# 16ChFNIRS.net
KiCad netlist of a schematic drawn in EAGLE
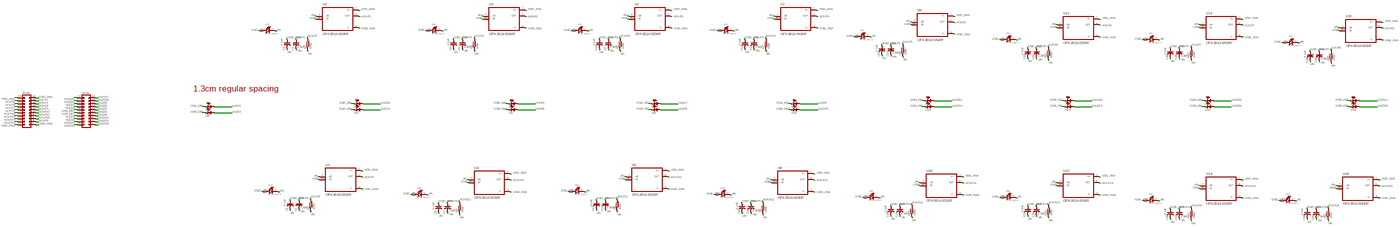
[diagram p0: schematic, sheet 1, overview]
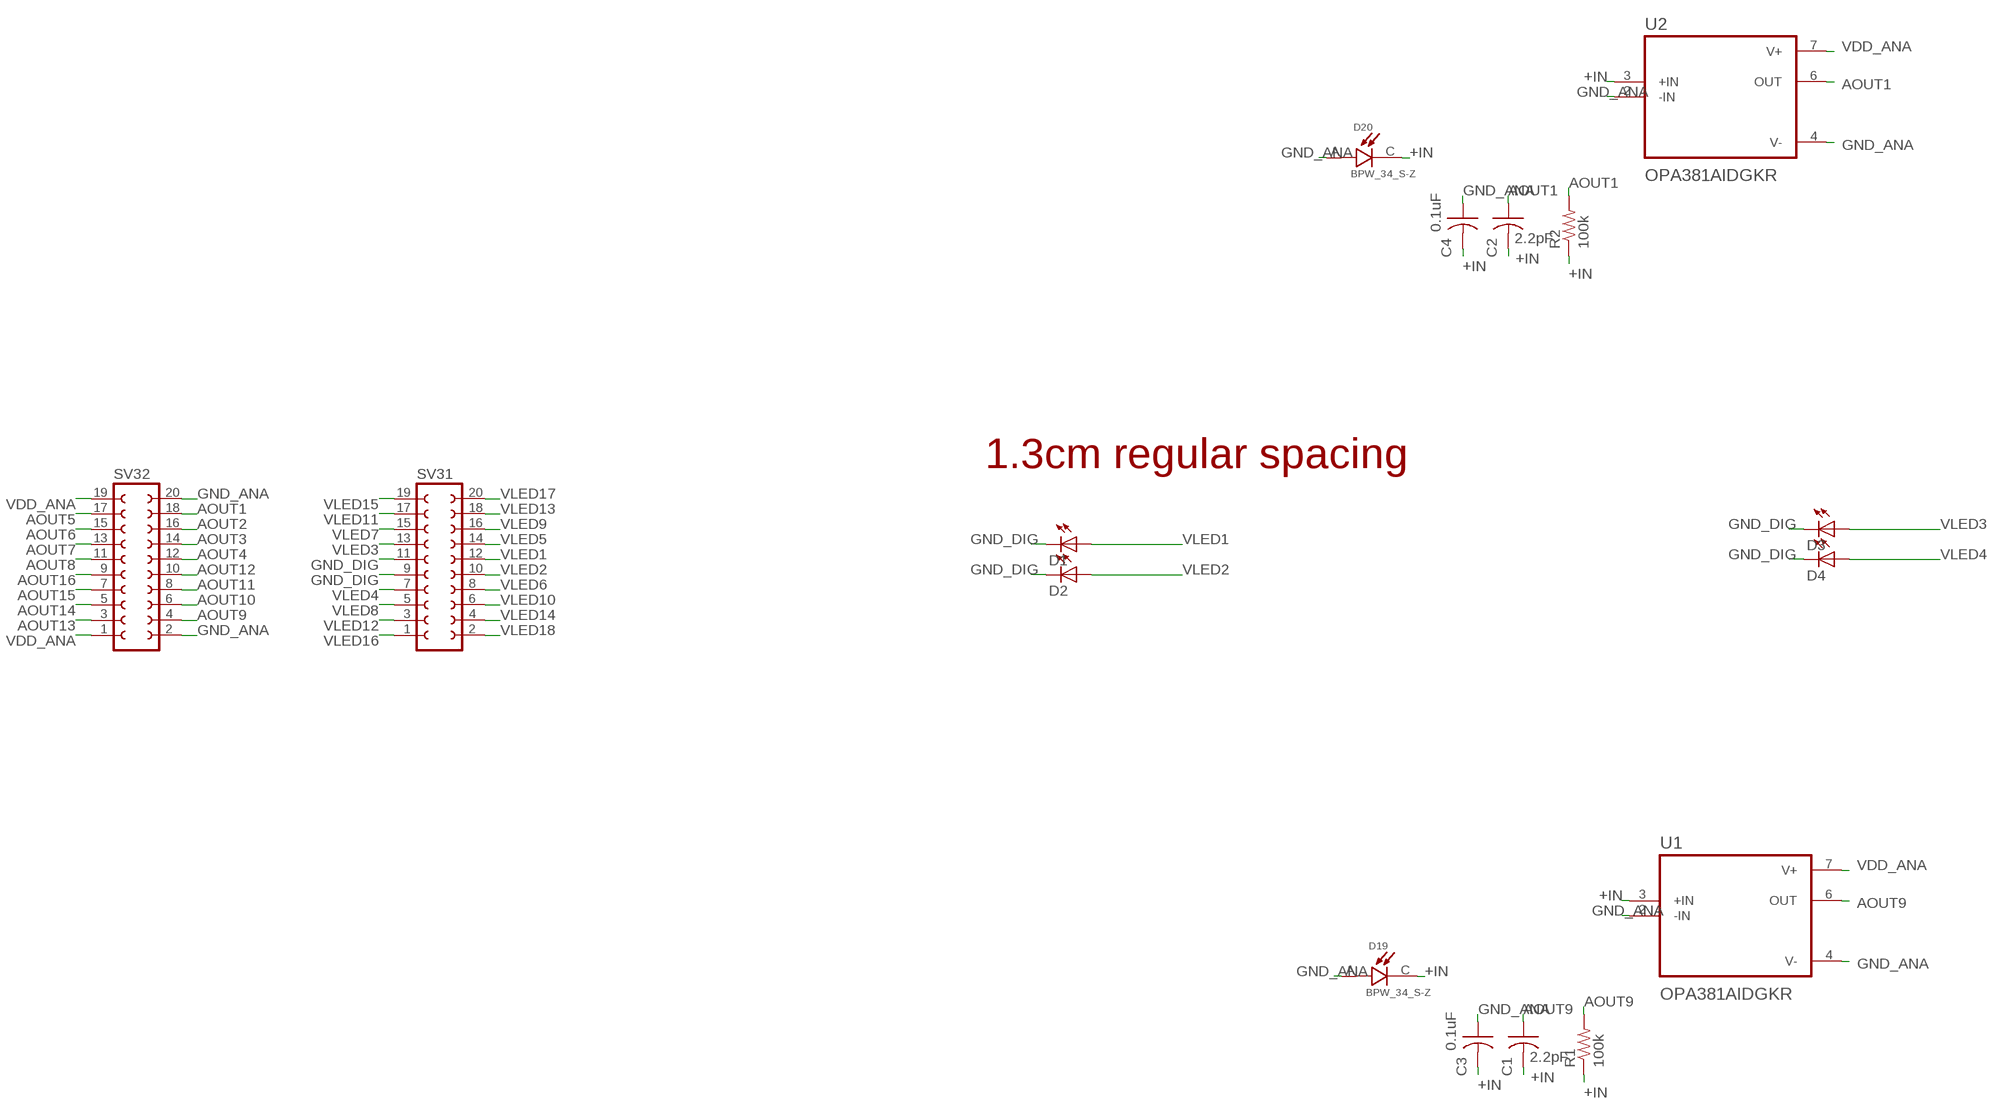
[diagram p1: schematic, sheet 1, part 1 of 4]
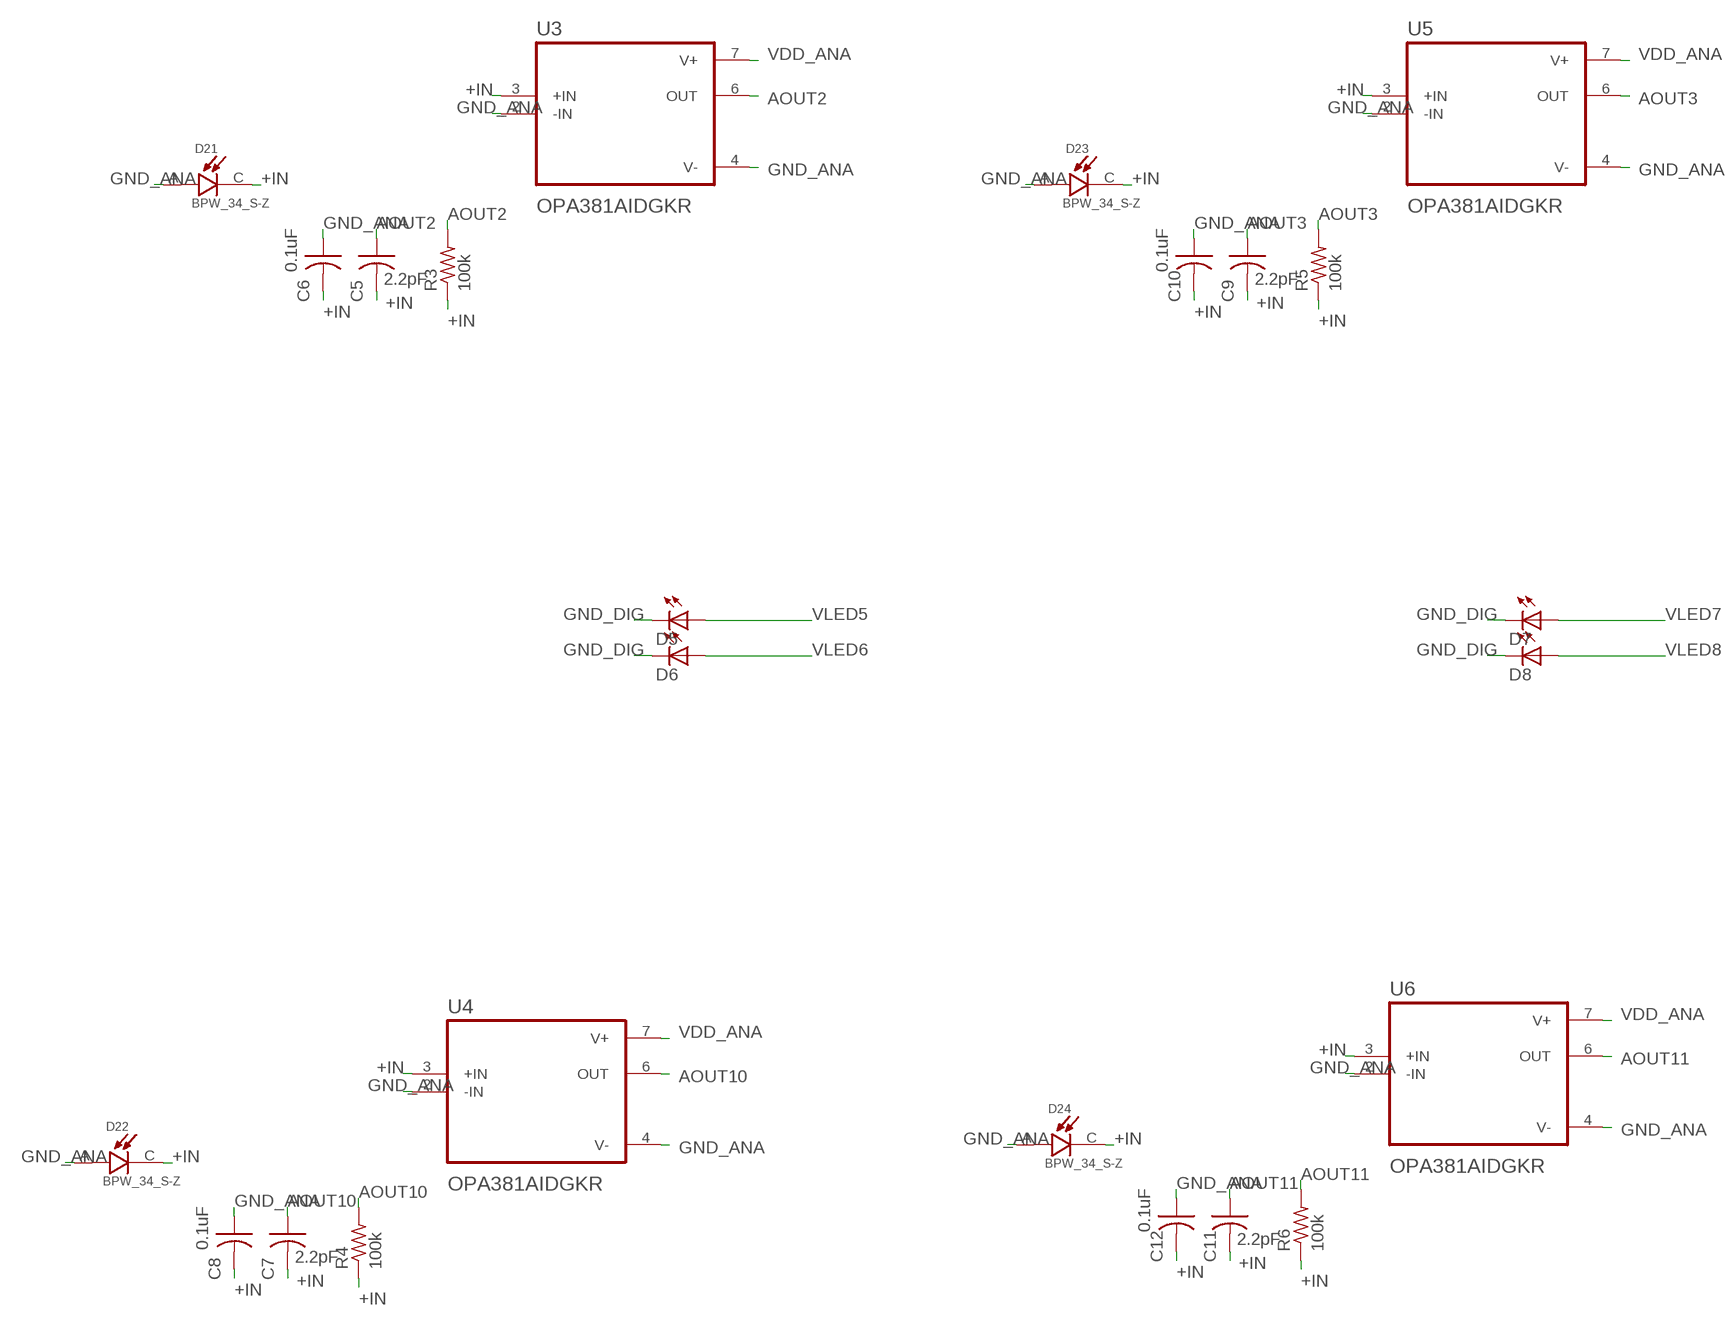
[diagram p2: schematic, sheet 1, part 2 of 4]
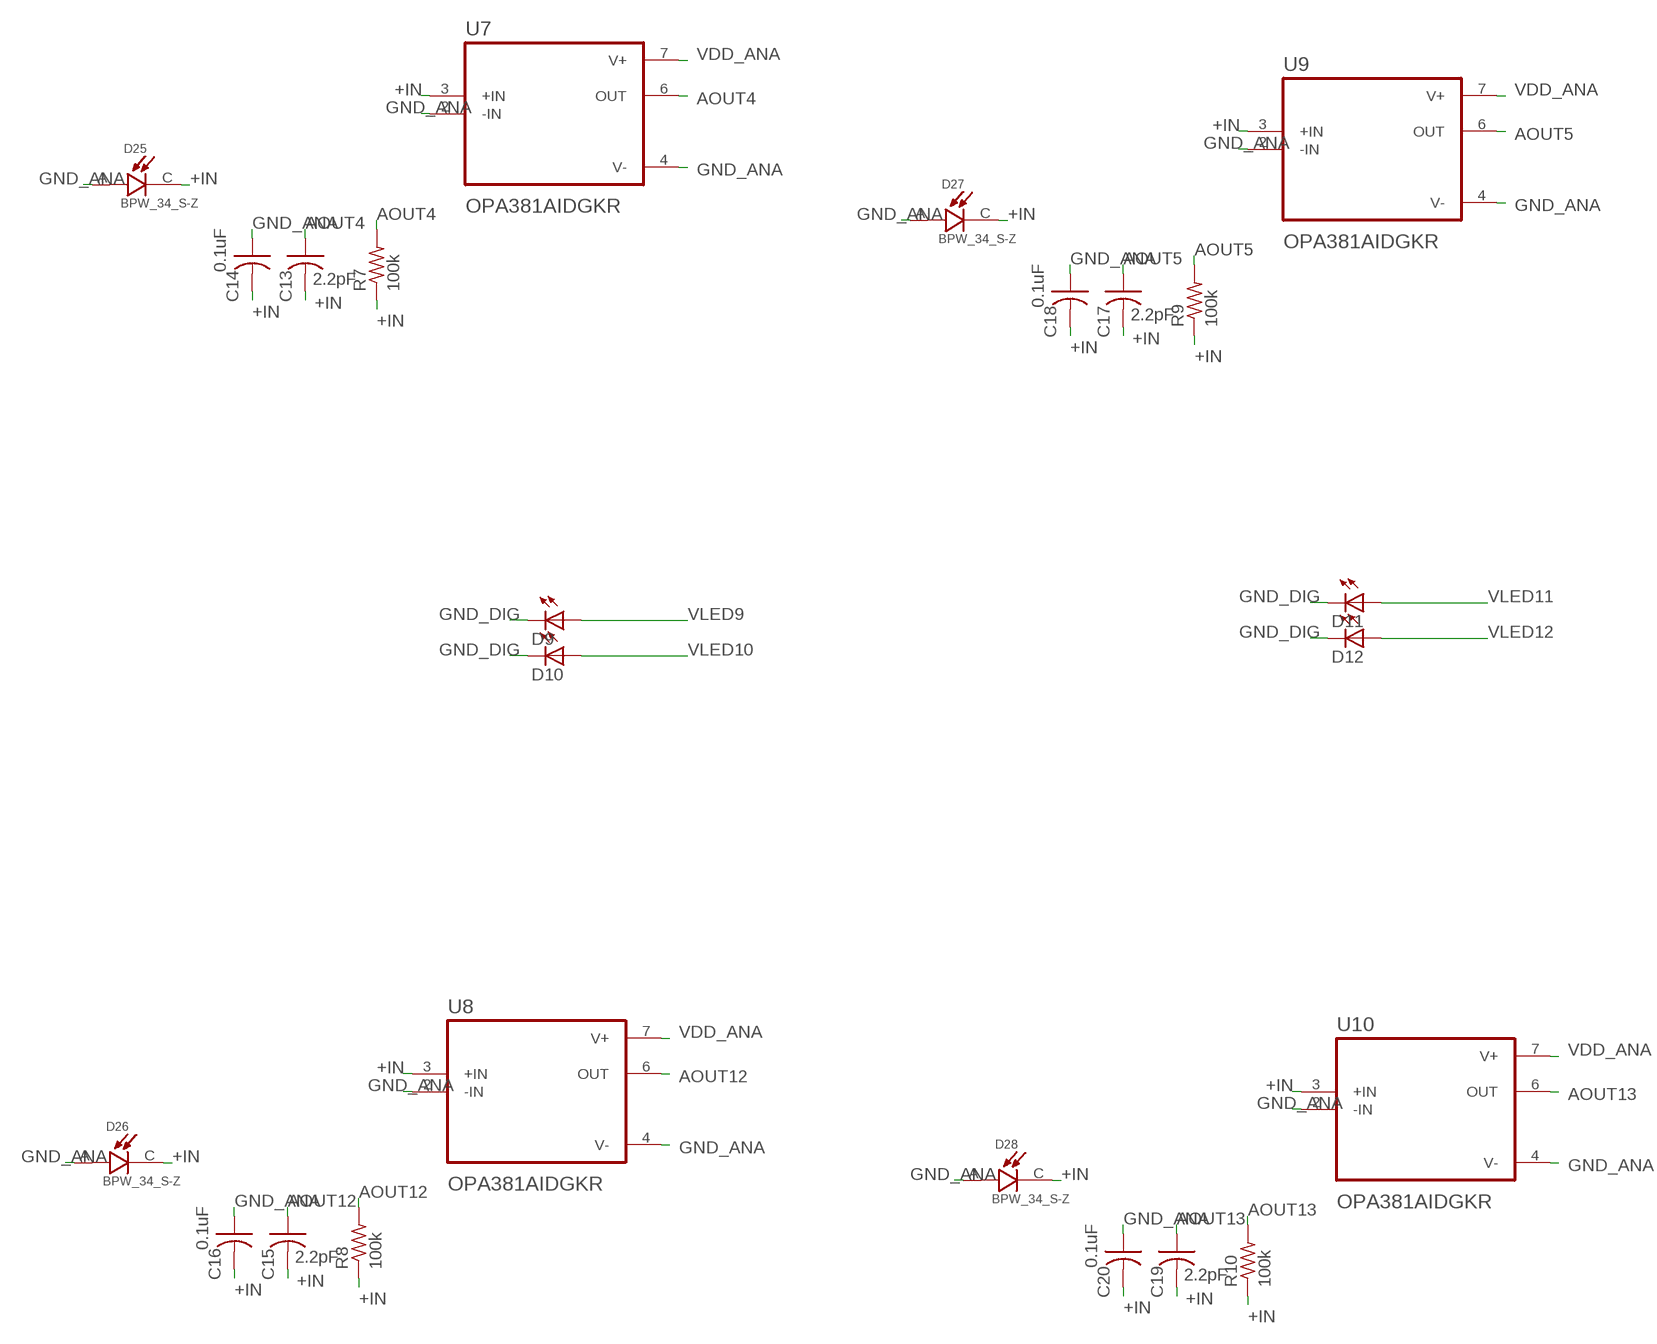
[diagram p3: schematic, sheet 1, part 3 of 4]
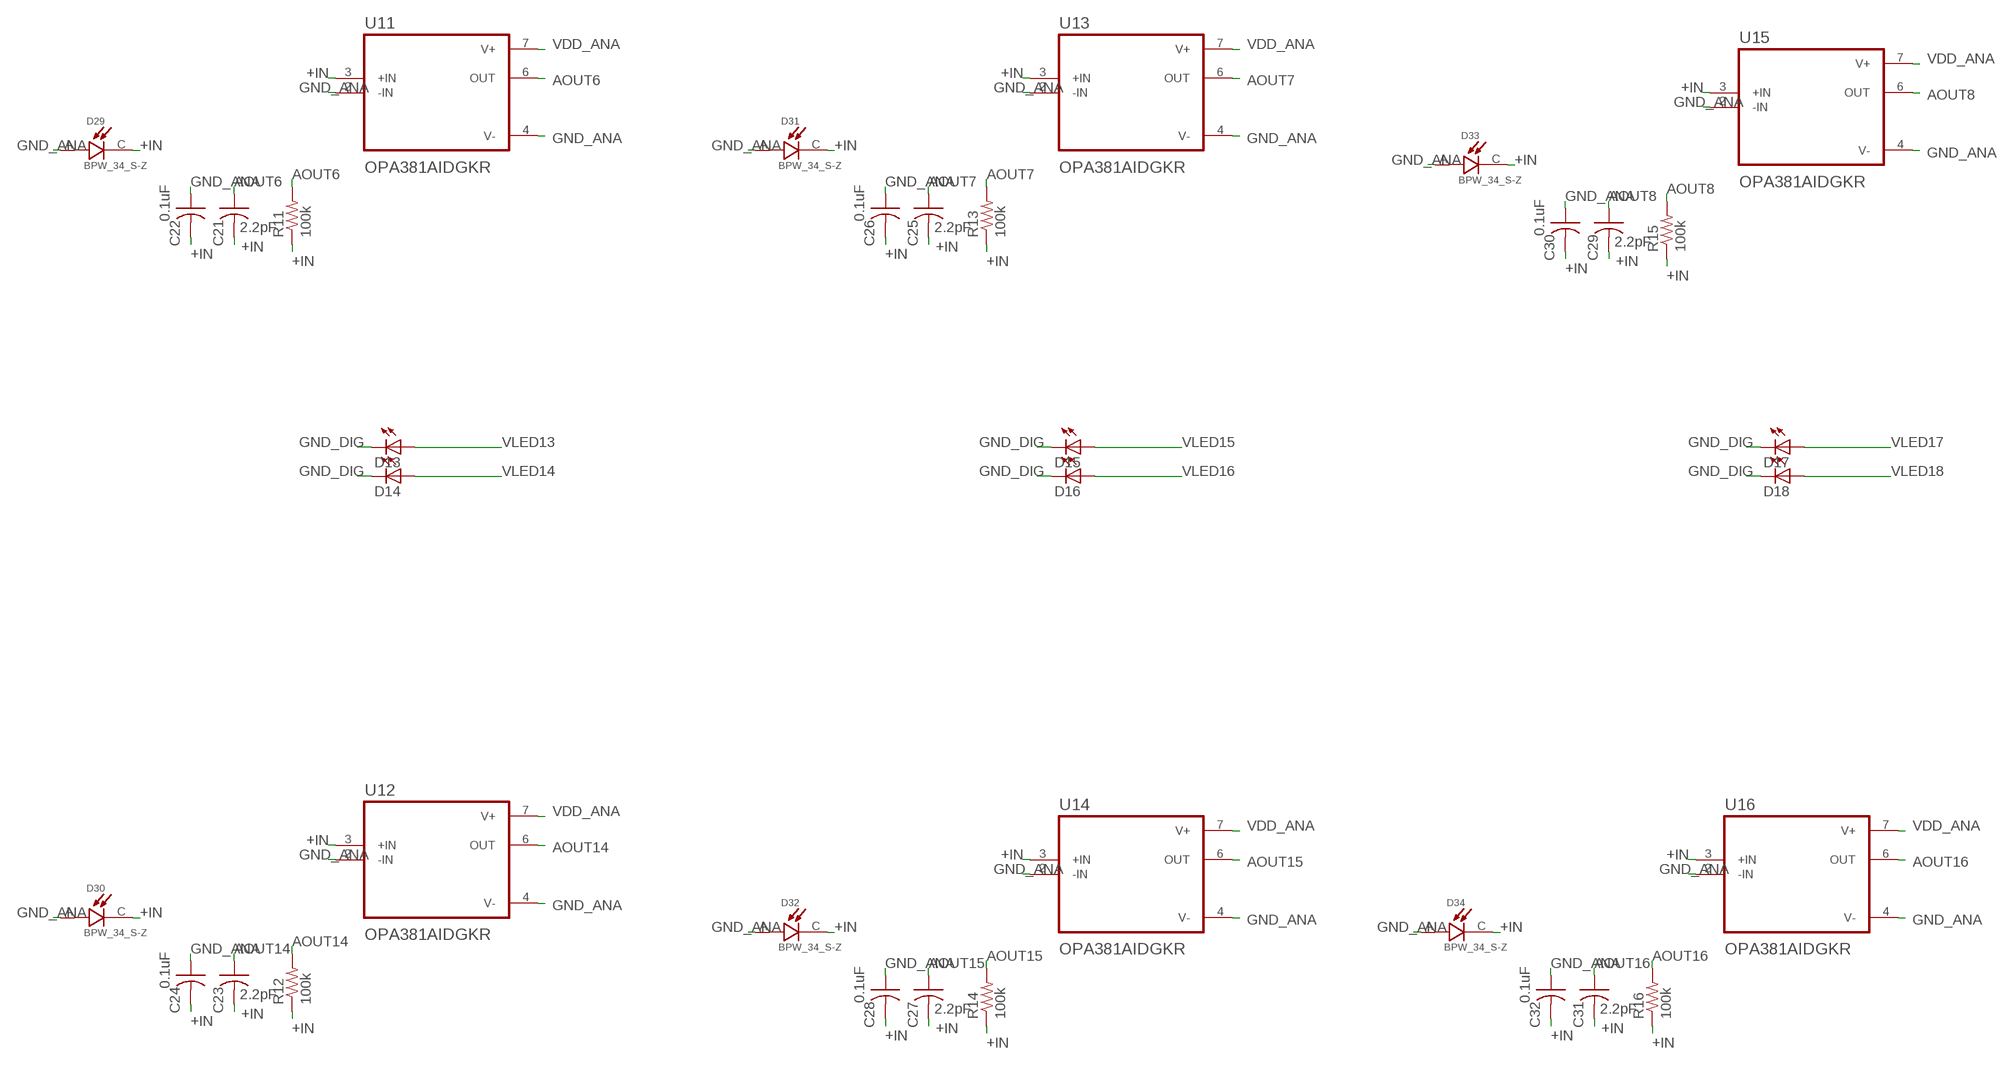
[diagram p4: schematic, sheet 1, part 4 of 4]

(export (version "E")
  (design (tool "Eeschema 10.0.6"))
  (components
    (comp (ref "C1")
      (value "2.2pF")
      (footprint "eagle-import:C0603K")
      (libsource (lib "eagle-import") (part "C-USC0603K"))
    )
    (comp (ref "C2")
      (value "2.2pF")
      (footprint "eagle-import:C0603K")
      (libsource (lib "eagle-import") (part "C-USC0603K"))
    )
    (comp (ref "C3")
      (value "0.1uF")
      (footprint "eagle-import:C0603K")
      (libsource (lib "eagle-import") (part "C-USC0603K"))
    )
    (comp (ref "C4")
      (value "0.1uF")
      (footprint "eagle-import:C0603K")
      (libsource (lib "eagle-import") (part "C-USC0603K"))
    )
    (comp (ref "C5")
      (value "2.2pF")
      (footprint "eagle-import:C0603K")
      (libsource (lib "eagle-import") (part "C-USC0603K"))
    )
    (comp (ref "C6")
      (value "0.1uF")
      (footprint "eagle-import:C0603K")
      (libsource (lib "eagle-import") (part "C-USC0603K"))
    )
    (comp (ref "C7")
      (value "2.2pF")
      (footprint "eagle-import:C0603K")
      (libsource (lib "eagle-import") (part "C-USC0603K"))
    )
    (comp (ref "C8")
      (value "0.1uF")
      (footprint "eagle-import:C0603K")
      (libsource (lib "eagle-import") (part "C-USC0603K"))
    )
    (comp (ref "C9")
      (value "2.2pF")
      (footprint "eagle-import:C0603K")
      (libsource (lib "eagle-import") (part "C-USC0603K"))
    )
    (comp (ref "C10")
      (value "0.1uF")
      (footprint "eagle-import:C0603K")
      (libsource (lib "eagle-import") (part "C-USC0603K"))
    )
    (comp (ref "C11")
      (value "2.2pF")
      (footprint "eagle-import:C0603K")
      (libsource (lib "eagle-import") (part "C-USC0603K"))
    )
    (comp (ref "C12")
      (value "0.1uF")
      (footprint "eagle-import:C0603K")
      (libsource (lib "eagle-import") (part "C-USC0603K"))
    )
    (comp (ref "C13")
      (value "2.2pF")
      (footprint "eagle-import:C0603K")
      (libsource (lib "eagle-import") (part "C-USC0603K"))
    )
    (comp (ref "C14")
      (value "0.1uF")
      (footprint "eagle-import:C0603K")
      (libsource (lib "eagle-import") (part "C-USC0603K"))
    )
    (comp (ref "C15")
      (value "2.2pF")
      (footprint "eagle-import:C0603K")
      (libsource (lib "eagle-import") (part "C-USC0603K"))
    )
    (comp (ref "C16")
      (value "0.1uF")
      (footprint "eagle-import:C0603K")
      (libsource (lib "eagle-import") (part "C-USC0603K"))
    )
    (comp (ref "C17")
      (value "2.2pF")
      (footprint "eagle-import:C0603K")
      (libsource (lib "eagle-import") (part "C-USC0603K"))
    )
    (comp (ref "C18")
      (value "0.1uF")
      (footprint "eagle-import:C0603K")
      (libsource (lib "eagle-import") (part "C-USC0603K"))
    )
    (comp (ref "C19")
      (value "2.2pF")
      (footprint "eagle-import:C0603K")
      (libsource (lib "eagle-import") (part "C-USC0603K"))
    )
    (comp (ref "C20")
      (value "0.1uF")
      (footprint "eagle-import:C0603K")
      (libsource (lib "eagle-import") (part "C-USC0603K"))
    )
    (comp (ref "C21")
      (value "2.2pF")
      (footprint "eagle-import:C0603K")
      (libsource (lib "eagle-import") (part "C-USC0603K"))
    )
    (comp (ref "C22")
      (value "0.1uF")
      (footprint "eagle-import:C0603K")
      (libsource (lib "eagle-import") (part "C-USC0603K"))
    )
    (comp (ref "C23")
      (value "2.2pF")
      (footprint "eagle-import:C0603K")
      (libsource (lib "eagle-import") (part "C-USC0603K"))
    )
    (comp (ref "C24")
      (value "0.1uF")
      (footprint "eagle-import:C0603K")
      (libsource (lib "eagle-import") (part "C-USC0603K"))
    )
    (comp (ref "C25")
      (value "2.2pF")
      (footprint "eagle-import:C0603K")
      (libsource (lib "eagle-import") (part "C-USC0603K"))
    )
    (comp (ref "C26")
      (value "0.1uF")
      (footprint "eagle-import:C0603K")
      (libsource (lib "eagle-import") (part "C-USC0603K"))
    )
    (comp (ref "C27")
      (value "2.2pF")
      (footprint "eagle-import:C0603K")
      (libsource (lib "eagle-import") (part "C-USC0603K"))
    )
    (comp (ref "C28")
      (value "0.1uF")
      (footprint "eagle-import:C0603K")
      (libsource (lib "eagle-import") (part "C-USC0603K"))
    )
    (comp (ref "C29")
      (value "2.2pF")
      (footprint "eagle-import:C0603K")
      (libsource (lib "eagle-import") (part "C-USC0603K"))
    )
    (comp (ref "C30")
      (value "0.1uF")
      (footprint "eagle-import:C0603K")
      (libsource (lib "eagle-import") (part "C-USC0603K"))
    )
    (comp (ref "C31")
      (value "2.2pF")
      (footprint "eagle-import:C0603K")
      (libsource (lib "eagle-import") (part "C-USC0603K"))
    )
    (comp (ref "C32")
      (value "0.1uF")
      (footprint "eagle-import:C0603K")
      (libsource (lib "eagle-import") (part "C-USC0603K"))
    )
    (comp (ref "D1")
      (value "LED1206")
      (footprint "eagle-import:LED-1206")
      (libsource (lib "eagle-import") (part "LED1206"))
    )
    (comp (ref "D2")
      (value "LED1206")
      (footprint "eagle-import:LED-1206")
      (libsource (lib "eagle-import") (part "LED1206"))
    )
    (comp (ref "D3")
      (value "LED1206")
      (footprint "eagle-import:LED-1206")
      (libsource (lib "eagle-import") (part "LED1206"))
    )
    (comp (ref "D4")
      (value "LED1206")
      (footprint "eagle-import:LED-1206")
      (libsource (lib "eagle-import") (part "LED1206"))
    )
    (comp (ref "D5")
      (value "LED1206")
      (footprint "eagle-import:LED-1206")
      (libsource (lib "eagle-import") (part "LED1206"))
    )
    (comp (ref "D6")
      (value "LED1206")
      (footprint "eagle-import:LED-1206")
      (libsource (lib "eagle-import") (part "LED1206"))
    )
    (comp (ref "D7")
      (value "LED1206")
      (footprint "eagle-import:LED-1206")
      (libsource (lib "eagle-import") (part "LED1206"))
    )
    (comp (ref "D8")
      (value "LED1206")
      (footprint "eagle-import:LED-1206")
      (libsource (lib "eagle-import") (part "LED1206"))
    )
    (comp (ref "D9")
      (value "LED1206")
      (footprint "eagle-import:LED-1206")
      (libsource (lib "eagle-import") (part "LED1206"))
    )
    (comp (ref "D10")
      (value "LED1206")
      (footprint "eagle-import:LED-1206")
      (libsource (lib "eagle-import") (part "LED1206"))
    )
    (comp (ref "D11")
      (value "LED1206")
      (footprint "eagle-import:LED-1206")
      (libsource (lib "eagle-import") (part "LED1206"))
    )
    (comp (ref "D12")
      (value "LED1206")
      (footprint "eagle-import:LED-1206")
      (libsource (lib "eagle-import") (part "LED1206"))
    )
    (comp (ref "D13")
      (value "LED1206")
      (footprint "eagle-import:LED-1206")
      (libsource (lib "eagle-import") (part "LED1206"))
    )
    (comp (ref "D14")
      (value "LED1206")
      (footprint "eagle-import:LED-1206")
      (libsource (lib "eagle-import") (part "LED1206"))
    )
    (comp (ref "D15")
      (value "LED1206")
      (footprint "eagle-import:LED-1206")
      (libsource (lib "eagle-import") (part "LED1206"))
    )
    (comp (ref "D16")
      (value "LED1206")
      (footprint "eagle-import:LED-1206")
      (libsource (lib "eagle-import") (part "LED1206"))
    )
    (comp (ref "D17")
      (value "LED1206")
      (footprint "eagle-import:LED-1206")
      (libsource (lib "eagle-import") (part "LED1206"))
    )
    (comp (ref "D18")
      (value "LED1206")
      (footprint "eagle-import:LED-1206")
      (libsource (lib "eagle-import") (part "LED1206"))
    )
    (comp (ref "D19")
      (value "BPW_34_S-Z")
      (footprint "eagle-import:DIO_BPW_34_S-Z")
      (fields (field (name "MF") "OSRAM Opto") (field (name "MP") "BPW 34 S-Z"))
      (libsource (lib "eagle-import") (part "BPW_34_S-Z"))
    )
    (comp (ref "D20")
      (value "BPW_34_S-Z")
      (footprint "eagle-import:DIO_BPW_34_S-Z")
      (fields (field (name "MF") "OSRAM Opto") (field (name "MP") "BPW 34 S-Z"))
      (libsource (lib "eagle-import") (part "BPW_34_S-Z"))
    )
    (comp (ref "D21")
      (value "BPW_34_S-Z")
      (footprint "eagle-import:DIO_BPW_34_S-Z")
      (fields (field (name "MF") "OSRAM Opto") (field (name "MP") "BPW 34 S-Z"))
      (libsource (lib "eagle-import") (part "BPW_34_S-Z"))
    )
    (comp (ref "D22")
      (value "BPW_34_S-Z")
      (footprint "eagle-import:DIO_BPW_34_S-Z")
      (fields (field (name "MF") "OSRAM Opto") (field (name "MP") "BPW 34 S-Z"))
      (libsource (lib "eagle-import") (part "BPW_34_S-Z"))
    )
    (comp (ref "D23")
      (value "BPW_34_S-Z")
      (footprint "eagle-import:DIO_BPW_34_S-Z")
      (fields (field (name "MF") "OSRAM Opto") (field (name "MP") "BPW 34 S-Z"))
      (libsource (lib "eagle-import") (part "BPW_34_S-Z"))
    )
    (comp (ref "D24")
      (value "BPW_34_S-Z")
      (footprint "eagle-import:DIO_BPW_34_S-Z")
      (fields (field (name "MF") "OSRAM Opto") (field (name "MP") "BPW 34 S-Z"))
      (libsource (lib "eagle-import") (part "BPW_34_S-Z"))
    )
    (comp (ref "D25")
      (value "BPW_34_S-Z")
      (footprint "eagle-import:DIO_BPW_34_S-Z")
      (fields (field (name "MF") "OSRAM Opto") (field (name "MP") "BPW 34 S-Z"))
      (libsource (lib "eagle-import") (part "BPW_34_S-Z"))
    )
    (comp (ref "D26")
      (value "BPW_34_S-Z")
      (footprint "eagle-import:DIO_BPW_34_S-Z")
      (fields (field (name "MF") "OSRAM Opto") (field (name "MP") "BPW 34 S-Z"))
      (libsource (lib "eagle-import") (part "BPW_34_S-Z"))
    )
    (comp (ref "D27")
      (value "BPW_34_S-Z")
      (footprint "eagle-import:DIO_BPW_34_S-Z")
      (fields (field (name "MF") "OSRAM Opto") (field (name "MP") "BPW 34 S-Z"))
      (libsource (lib "eagle-import") (part "BPW_34_S-Z"))
    )
    (comp (ref "D28")
      (value "BPW_34_S-Z")
      (footprint "eagle-import:DIO_BPW_34_S-Z")
      (fields (field (name "MF") "OSRAM Opto") (field (name "MP") "BPW 34 S-Z"))
      (libsource (lib "eagle-import") (part "BPW_34_S-Z"))
    )
    (comp (ref "D29")
      (value "BPW_34_S-Z")
      (footprint "eagle-import:DIO_BPW_34_S-Z")
      (fields (field (name "MF") "OSRAM Opto") (field (name "MP") "BPW 34 S-Z"))
      (libsource (lib "eagle-import") (part "BPW_34_S-Z"))
    )
    (comp (ref "D30")
      (value "BPW_34_S-Z")
      (footprint "eagle-import:DIO_BPW_34_S-Z")
      (fields (field (name "MF") "OSRAM Opto") (field (name "MP") "BPW 34 S-Z"))
      (libsource (lib "eagle-import") (part "BPW_34_S-Z"))
    )
    (comp (ref "D31")
      (value "BPW_34_S-Z")
      (footprint "eagle-import:DIO_BPW_34_S-Z")
      (fields (field (name "MF") "OSRAM Opto") (field (name "MP") "BPW 34 S-Z"))
      (libsource (lib "eagle-import") (part "BPW_34_S-Z"))
    )
    (comp (ref "D32")
      (value "BPW_34_S-Z")
      (footprint "eagle-import:DIO_BPW_34_S-Z")
      (fields (field (name "MF") "OSRAM Opto") (field (name "MP") "BPW 34 S-Z"))
      (libsource (lib "eagle-import") (part "BPW_34_S-Z"))
    )
    (comp (ref "D33")
      (value "BPW_34_S-Z")
      (footprint "eagle-import:DIO_BPW_34_S-Z")
      (fields (field (name "MF") "OSRAM Opto") (field (name "MP") "BPW 34 S-Z"))
      (libsource (lib "eagle-import") (part "BPW_34_S-Z"))
    )
    (comp (ref "D34")
      (value "BPW_34_S-Z")
      (footprint "eagle-import:DIO_BPW_34_S-Z")
      (fields (field (name "MF") "OSRAM Opto") (field (name "MP") "BPW 34 S-Z"))
      (libsource (lib "eagle-import") (part "BPW_34_S-Z"))
    )
    (comp (ref "R1")
      (value "100k")
      (footprint "eagle-import:R0603")
      (libsource (lib "eagle-import") (part "R-US_R0603"))
    )
    (comp (ref "R2")
      (value "100k")
      (footprint "eagle-import:R0603")
      (libsource (lib "eagle-import") (part "R-US_R0603"))
    )
    (comp (ref "R3")
      (value "100k")
      (footprint "eagle-import:R0603")
      (libsource (lib "eagle-import") (part "R-US_R0603"))
    )
    (comp (ref "R4")
      (value "100k")
      (footprint "eagle-import:R0603")
      (libsource (lib "eagle-import") (part "R-US_R0603"))
    )
    (comp (ref "R5")
      (value "100k")
      (footprint "eagle-import:R0603")
      (libsource (lib "eagle-import") (part "R-US_R0603"))
    )
    (comp (ref "R6")
      (value "100k")
      (footprint "eagle-import:R0603")
      (libsource (lib "eagle-import") (part "R-US_R0603"))
    )
    (comp (ref "R7")
      (value "100k")
      (footprint "eagle-import:R0603")
      (libsource (lib "eagle-import") (part "R-US_R0603"))
    )
    (comp (ref "R8")
      (value "100k")
      (footprint "eagle-import:R0603")
      (libsource (lib "eagle-import") (part "R-US_R0603"))
    )
    (comp (ref "R9")
      (value "100k")
      (footprint "eagle-import:R0603")
      (libsource (lib "eagle-import") (part "R-US_R0603"))
    )
    (comp (ref "R10")
      (value "100k")
      (footprint "eagle-import:R0603")
      (libsource (lib "eagle-import") (part "R-US_R0603"))
    )
    (comp (ref "R11")
      (value "100k")
      (footprint "eagle-import:R0603")
      (libsource (lib "eagle-import") (part "R-US_R0603"))
    )
    (comp (ref "R12")
      (value "100k")
      (footprint "eagle-import:R0603")
      (libsource (lib "eagle-import") (part "R-US_R0603"))
    )
    (comp (ref "R13")
      (value "100k")
      (footprint "eagle-import:R0603")
      (libsource (lib "eagle-import") (part "R-US_R0603"))
    )
    (comp (ref "R14")
      (value "100k")
      (footprint "eagle-import:R0603")
      (libsource (lib "eagle-import") (part "R-US_R0603"))
    )
    (comp (ref "R15")
      (value "100k")
      (footprint "eagle-import:R0603")
      (libsource (lib "eagle-import") (part "R-US_R0603"))
    )
    (comp (ref "R16")
      (value "100k")
      (footprint "eagle-import:R0603")
      (libsource (lib "eagle-import") (part "R-US_R0603"))
    )
    (comp (ref "SV31")
      (value "FE10-2")
      (footprint "eagle-import:FE10-2")
      (libsource (lib "eagle-import") (part "FE10-2"))
    )
    (comp (ref "SV32")
      (value "FE10-2")
      (footprint "eagle-import:FE10-2")
      (libsource (lib "eagle-import") (part "FE10-2"))
    )
    (comp (ref "U1")
      (value "OPA381AIDGKR")
      (footprint "eagle-import:SOP65P490X110-8N")
      (fields (field (name "MF") "Texas Instruments"))
      (libsource (lib "eagle-import") (part "OPA381AIDGKR"))
    )
    (comp (ref "U2")
      (value "OPA381AIDGKR")
      (footprint "eagle-import:SOP65P490X110-8N")
      (fields (field (name "MF") "Texas Instruments"))
      (libsource (lib "eagle-import") (part "OPA381AIDGKR"))
    )
    (comp (ref "U3")
      (value "OPA381AIDGKR")
      (footprint "eagle-import:SOP65P490X110-8N")
      (fields (field (name "MF") "Texas Instruments"))
      (libsource (lib "eagle-import") (part "OPA381AIDGKR"))
    )
    (comp (ref "U4")
      (value "OPA381AIDGKR")
      (footprint "eagle-import:SOP65P490X110-8N")
      (fields (field (name "MF") "Texas Instruments"))
      (libsource (lib "eagle-import") (part "OPA381AIDGKR"))
    )
    (comp (ref "U5")
      (value "OPA381AIDGKR")
      (footprint "eagle-import:SOP65P490X110-8N")
      (fields (field (name "MF") "Texas Instruments"))
      (libsource (lib "eagle-import") (part "OPA381AIDGKR"))
    )
    (comp (ref "U6")
      (value "OPA381AIDGKR")
      (footprint "eagle-import:SOP65P490X110-8N")
      (fields (field (name "MF") "Texas Instruments"))
      (libsource (lib "eagle-import") (part "OPA381AIDGKR"))
    )
    (comp (ref "U7")
      (value "OPA381AIDGKR")
      (footprint "eagle-import:SOP65P490X110-8N")
      (fields (field (name "MF") "Texas Instruments"))
      (libsource (lib "eagle-import") (part "OPA381AIDGKR"))
    )
    (comp (ref "U8")
      (value "OPA381AIDGKR")
      (footprint "eagle-import:SOP65P490X110-8N")
      (fields (field (name "MF") "Texas Instruments"))
      (libsource (lib "eagle-import") (part "OPA381AIDGKR"))
    )
    (comp (ref "U9")
      (value "OPA381AIDGKR")
      (footprint "eagle-import:SOP65P490X110-8N")
      (fields (field (name "MF") "Texas Instruments"))
      (libsource (lib "eagle-import") (part "OPA381AIDGKR"))
    )
    (comp (ref "U10")
      (value "OPA381AIDGKR")
      (footprint "eagle-import:SOP65P490X110-8N")
      (fields (field (name "MF") "Texas Instruments"))
      (libsource (lib "eagle-import") (part "OPA381AIDGKR"))
    )
    (comp (ref "U11")
      (value "OPA381AIDGKR")
      (footprint "eagle-import:SOP65P490X110-8N")
      (fields (field (name "MF") "Texas Instruments"))
      (libsource (lib "eagle-import") (part "OPA381AIDGKR"))
    )
    (comp (ref "U12")
      (value "OPA381AIDGKR")
      (footprint "eagle-import:SOP65P490X110-8N")
      (fields (field (name "MF") "Texas Instruments"))
      (libsource (lib "eagle-import") (part "OPA381AIDGKR"))
    )
    (comp (ref "U13")
      (value "OPA381AIDGKR")
      (footprint "eagle-import:SOP65P490X110-8N")
      (fields (field (name "MF") "Texas Instruments"))
      (libsource (lib "eagle-import") (part "OPA381AIDGKR"))
    )
    (comp (ref "U14")
      (value "OPA381AIDGKR")
      (footprint "eagle-import:SOP65P490X110-8N")
      (fields (field (name "MF") "Texas Instruments"))
      (libsource (lib "eagle-import") (part "OPA381AIDGKR"))
    )
    (comp (ref "U15")
      (value "OPA381AIDGKR")
      (footprint "eagle-import:SOP65P490X110-8N")
      (fields (field (name "MF") "Texas Instruments"))
      (libsource (lib "eagle-import") (part "OPA381AIDGKR"))
    )
    (comp (ref "U16")
      (value "OPA381AIDGKR")
      (footprint "eagle-import:SOP65P490X110-8N")
      (fields (field (name "MF") "Texas Instruments"))
      (libsource (lib "eagle-import") (part "OPA381AIDGKR"))
    )
  )
  (nets
    (net (code "1") (name "/+IN") (class "Default")
      (node (ref "C1") (pin "2") (pinfunction "2_2") (pintype "passive"))
      (node (ref "C10") (pin "2") (pinfunction "2_2") (pintype "passive"))
      (node (ref "C11") (pin "2") (pinfunction "2_2") (pintype "passive"))
      (node (ref "C12") (pin "2") (pinfunction "2_2") (pintype "passive"))
      (node (ref "C13") (pin "2") (pinfunction "2_2") (pintype "passive"))
      (node (ref "C14") (pin "2") (pinfunction "2_2") (pintype "passive"))
      (node (ref "C15") (pin "2") (pinfunction "2_2") (pintype "passive"))
      (node (ref "C16") (pin "2") (pinfunction "2_2") (pintype "passive"))
      (node (ref "C17") (pin "2") (pinfunction "2_2") (pintype "passive"))
      (node (ref "C18") (pin "2") (pinfunction "2_2") (pintype "passive"))
      (node (ref "C19") (pin "2") (pinfunction "2_2") (pintype "passive"))
      (node (ref "C2") (pin "2") (pinfunction "2_2") (pintype "passive"))
      (node (ref "C20") (pin "2") (pinfunction "2_2") (pintype "passive"))
      (node (ref "C21") (pin "2") (pinfunction "2_2") (pintype "passive"))
      (node (ref "C22") (pin "2") (pinfunction "2_2") (pintype "passive"))
      (node (ref "C23") (pin "2") (pinfunction "2_2") (pintype "passive"))
      (node (ref "C24") (pin "2") (pinfunction "2_2") (pintype "passive"))
      (node (ref "C25") (pin "2") (pinfunction "2_2") (pintype "passive"))
      (node (ref "C26") (pin "2") (pinfunction "2_2") (pintype "passive"))
      (node (ref "C27") (pin "2") (pinfunction "2_2") (pintype "passive"))
      (node (ref "C28") (pin "2") (pinfunction "2_2") (pintype "passive"))
      (node (ref "C29") (pin "2") (pinfunction "2_2") (pintype "passive"))
      (node (ref "C3") (pin "2") (pinfunction "2_2") (pintype "passive"))
      (node (ref "C30") (pin "2") (pinfunction "2_2") (pintype "passive"))
      (node (ref "C31") (pin "2") (pinfunction "2_2") (pintype "passive"))
      (node (ref "C32") (pin "2") (pinfunction "2_2") (pintype "passive"))
      (node (ref "C4") (pin "2") (pinfunction "2_2") (pintype "passive"))
      (node (ref "C5") (pin "2") (pinfunction "2_2") (pintype "passive"))
      (node (ref "C6") (pin "2") (pinfunction "2_2") (pintype "passive"))
      (node (ref "C7") (pin "2") (pinfunction "2_2") (pintype "passive"))
      (node (ref "C8") (pin "2") (pinfunction "2_2") (pintype "passive"))
      (node (ref "C9") (pin "2") (pinfunction "2_2") (pintype "passive"))
      (node (ref "D19") (pin "C") (pinfunction "C_C") (pintype "passive"))
      (node (ref "D20") (pin "C") (pinfunction "C_C") (pintype "passive"))
      (node (ref "D21") (pin "C") (pinfunction "C_C") (pintype "passive"))
      (node (ref "D22") (pin "C") (pinfunction "C_C") (pintype "passive"))
      (node (ref "D23") (pin "C") (pinfunction "C_C") (pintype "passive"))
      (node (ref "D24") (pin "C") (pinfunction "C_C") (pintype "passive"))
      (node (ref "D25") (pin "C") (pinfunction "C_C") (pintype "passive"))
      (node (ref "D26") (pin "C") (pinfunction "C_C") (pintype "passive"))
      (node (ref "D27") (pin "C") (pinfunction "C_C") (pintype "passive"))
      (node (ref "D28") (pin "C") (pinfunction "C_C") (pintype "passive"))
      (node (ref "D29") (pin "C") (pinfunction "C_C") (pintype "passive"))
      (node (ref "D30") (pin "C") (pinfunction "C_C") (pintype "passive"))
      (node (ref "D31") (pin "C") (pinfunction "C_C") (pintype "passive"))
      (node (ref "D32") (pin "C") (pinfunction "C_C") (pintype "passive"))
      (node (ref "D33") (pin "C") (pinfunction "C_C") (pintype "passive"))
      (node (ref "D34") (pin "C") (pinfunction "C_C") (pintype "passive"))
      (node (ref "R1") (pin "1") (pinfunction "1_1") (pintype "passive"))
      (node (ref "R10") (pin "1") (pinfunction "1_1") (pintype "passive"))
      (node (ref "R11") (pin "1") (pinfunction "1_1") (pintype "passive"))
      (node (ref "R12") (pin "1") (pinfunction "1_1") (pintype "passive"))
      (node (ref "R13") (pin "1") (pinfunction "1_1") (pintype "passive"))
      (node (ref "R14") (pin "1") (pinfunction "1_1") (pintype "passive"))
      (node (ref "R15") (pin "1") (pinfunction "1_1") (pintype "passive"))
      (node (ref "R16") (pin "1") (pinfunction "1_1") (pintype "passive"))
      (node (ref "R2") (pin "1") (pinfunction "1_1") (pintype "passive"))
      (node (ref "R3") (pin "1") (pinfunction "1_1") (pintype "passive"))
      (node (ref "R4") (pin "1") (pinfunction "1_1") (pintype "passive"))
      (node (ref "R5") (pin "1") (pinfunction "1_1") (pintype "passive"))
      (node (ref "R6") (pin "1") (pinfunction "1_1") (pintype "passive"))
      (node (ref "R7") (pin "1") (pinfunction "1_1") (pintype "passive"))
      (node (ref "R8") (pin "1") (pinfunction "1_1") (pintype "passive"))
      (node (ref "R9") (pin "1") (pinfunction "1_1") (pintype "passive"))
      (node (ref "U1") (pin "3") (pinfunction "+IN_3") (pintype "input"))
      (node (ref "U10") (pin "3") (pinfunction "+IN_3") (pintype "input"))
      (node (ref "U11") (pin "3") (pinfunction "+IN_3") (pintype "input"))
      (node (ref "U12") (pin "3") (pinfunction "+IN_3") (pintype "input"))
      (node (ref "U13") (pin "3") (pinfunction "+IN_3") (pintype "input"))
      (node (ref "U14") (pin "3") (pinfunction "+IN_3") (pintype "input"))
      (node (ref "U15") (pin "3") (pinfunction "+IN_3") (pintype "input"))
      (node (ref "U16") (pin "3") (pinfunction "+IN_3") (pintype "input"))
      (node (ref "U2") (pin "3") (pinfunction "+IN_3") (pintype "input"))
      (node (ref "U3") (pin "3") (pinfunction "+IN_3") (pintype "input"))
      (node (ref "U4") (pin "3") (pinfunction "+IN_3") (pintype "input"))
      (node (ref "U5") (pin "3") (pinfunction "+IN_3") (pintype "input"))
      (node (ref "U6") (pin "3") (pinfunction "+IN_3") (pintype "input"))
      (node (ref "U7") (pin "3") (pinfunction "+IN_3") (pintype "input"))
      (node (ref "U8") (pin "3") (pinfunction "+IN_3") (pintype "input"))
      (node (ref "U9") (pin "3") (pinfunction "+IN_3") (pintype "input"))
    )
    (net (code "2") (name "/AOUT1") (class "Default")
      (node (ref "C2") (pin "1") (pinfunction "1_1") (pintype "passive"))
      (node (ref "R2") (pin "2") (pinfunction "2_2") (pintype "passive"))
      (node (ref "SV32") (pin "18") (pinfunction "18_18") (pintype "passive"))
      (node (ref "U2") (pin "6") (pinfunction "OUT_6") (pintype "output"))
    )
    (net (code "3") (name "/AOUT2") (class "Default")
      (node (ref "C5") (pin "1") (pinfunction "1_1") (pintype "passive"))
      (node (ref "R3") (pin "2") (pinfunction "2_2") (pintype "passive"))
      (node (ref "SV32") (pin "16") (pinfunction "16_16") (pintype "passive"))
      (node (ref "U3") (pin "6") (pinfunction "OUT_6") (pintype "output"))
    )
    (net (code "4") (name "/AOUT3") (class "Default")
      (node (ref "C9") (pin "1") (pinfunction "1_1") (pintype "passive"))
      (node (ref "R5") (pin "2") (pinfunction "2_2") (pintype "passive"))
      (node (ref "SV32") (pin "14") (pinfunction "14_14") (pintype "passive"))
      (node (ref "U5") (pin "6") (pinfunction "OUT_6") (pintype "output"))
    )
    (net (code "5") (name "/AOUT4") (class "Default")
      (node (ref "C13") (pin "1") (pinfunction "1_1") (pintype "passive"))
      (node (ref "R7") (pin "2") (pinfunction "2_2") (pintype "passive"))
      (node (ref "SV32") (pin "12") (pinfunction "12_12") (pintype "passive"))
      (node (ref "U7") (pin "6") (pinfunction "OUT_6") (pintype "output"))
    )
    (net (code "6") (name "/AOUT5") (class "Default")
      (node (ref "C17") (pin "1") (pinfunction "1_1") (pintype "passive"))
      (node (ref "R9") (pin "2") (pinfunction "2_2") (pintype "passive"))
      (node (ref "SV32") (pin "17") (pinfunction "17_17") (pintype "passive"))
      (node (ref "U9") (pin "6") (pinfunction "OUT_6") (pintype "output"))
    )
    (net (code "7") (name "/AOUT6") (class "Default")
      (node (ref "C21") (pin "1") (pinfunction "1_1") (pintype "passive"))
      (node (ref "R11") (pin "2") (pinfunction "2_2") (pintype "passive"))
      (node (ref "SV32") (pin "15") (pinfunction "15_15") (pintype "passive"))
      (node (ref "U11") (pin "6") (pinfunction "OUT_6") (pintype "output"))
    )
    (net (code "8") (name "/AOUT7") (class "Default")
      (node (ref "C25") (pin "1") (pinfunction "1_1") (pintype "passive"))
      (node (ref "R13") (pin "2") (pinfunction "2_2") (pintype "passive"))
      (node (ref "SV32") (pin "13") (pinfunction "13_13") (pintype "passive"))
      (node (ref "U13") (pin "6") (pinfunction "OUT_6") (pintype "output"))
    )
    (net (code "9") (name "/AOUT8") (class "Default")
      (node (ref "C29") (pin "1") (pinfunction "1_1") (pintype "passive"))
      (node (ref "R15") (pin "2") (pinfunction "2_2") (pintype "passive"))
      (node (ref "SV32") (pin "11") (pinfunction "11_11") (pintype "passive"))
      (node (ref "U15") (pin "6") (pinfunction "OUT_6") (pintype "output"))
    )
    (net (code "10") (name "/AOUT9") (class "Default")
      (node (ref "C1") (pin "1") (pinfunction "1_1") (pintype "passive"))
      (node (ref "R1") (pin "2") (pinfunction "2_2") (pintype "passive"))
      (node (ref "SV32") (pin "4") (pinfunction "4_4") (pintype "passive"))
      (node (ref "U1") (pin "6") (pinfunction "OUT_6") (pintype "output"))
    )
    (net (code "11") (name "/AOUT10") (class "Default")
      (node (ref "C7") (pin "1") (pinfunction "1_1") (pintype "passive"))
      (node (ref "R4") (pin "2") (pinfunction "2_2") (pintype "passive"))
      (node (ref "SV32") (pin "6") (pinfunction "6_6") (pintype "passive"))
      (node (ref "U4") (pin "6") (pinfunction "OUT_6") (pintype "output"))
    )
    (net (code "12") (name "/AOUT11") (class "Default")
      (node (ref "C11") (pin "1") (pinfunction "1_1") (pintype "passive"))
      (node (ref "R6") (pin "2") (pinfunction "2_2") (pintype "passive"))
      (node (ref "SV32") (pin "8") (pinfunction "8_8") (pintype "passive"))
      (node (ref "U6") (pin "6") (pinfunction "OUT_6") (pintype "output"))
    )
    (net (code "13") (name "/AOUT12") (class "Default")
      (node (ref "C15") (pin "1") (pinfunction "1_1") (pintype "passive"))
      (node (ref "R8") (pin "2") (pinfunction "2_2") (pintype "passive"))
      (node (ref "SV32") (pin "10") (pinfunction "10_10") (pintype "passive"))
      (node (ref "U8") (pin "6") (pinfunction "OUT_6") (pintype "output"))
    )
    (net (code "14") (name "/AOUT13") (class "Default")
      (node (ref "C19") (pin "1") (pinfunction "1_1") (pintype "passive"))
      (node (ref "R10") (pin "2") (pinfunction "2_2") (pintype "passive"))
      (node (ref "SV32") (pin "3") (pinfunction "3_3") (pintype "passive"))
      (node (ref "U10") (pin "6") (pinfunction "OUT_6") (pintype "output"))
    )
    (net (code "15") (name "/AOUT14") (class "Default")
      (node (ref "C23") (pin "1") (pinfunction "1_1") (pintype "passive"))
      (node (ref "R12") (pin "2") (pinfunction "2_2") (pintype "passive"))
      (node (ref "SV32") (pin "5") (pinfunction "5_5") (pintype "passive"))
      (node (ref "U12") (pin "6") (pinfunction "OUT_6") (pintype "output"))
    )
    (net (code "16") (name "/AOUT15") (class "Default")
      (node (ref "C27") (pin "1") (pinfunction "1_1") (pintype "passive"))
      (node (ref "R14") (pin "2") (pinfunction "2_2") (pintype "passive"))
      (node (ref "SV32") (pin "7") (pinfunction "7_7") (pintype "passive"))
      (node (ref "U14") (pin "6") (pinfunction "OUT_6") (pintype "output"))
    )
    (net (code "17") (name "/AOUT16") (class "Default")
      (node (ref "C31") (pin "1") (pinfunction "1_1") (pintype "passive"))
      (node (ref "R16") (pin "2") (pinfunction "2_2") (pintype "passive"))
      (node (ref "SV32") (pin "9") (pinfunction "9_9") (pintype "passive"))
      (node (ref "U16") (pin "6") (pinfunction "OUT_6") (pintype "output"))
    )
    (net (code "18") (name "/GND_ANA") (class "Default")
      (node (ref "C10") (pin "1") (pinfunction "1_1") (pintype "passive"))
      (node (ref "C12") (pin "1") (pinfunction "1_1") (pintype "passive"))
      (node (ref "C14") (pin "1") (pinfunction "1_1") (pintype "passive"))
      (node (ref "C16") (pin "1") (pinfunction "1_1") (pintype "passive"))
      (node (ref "C18") (pin "1") (pinfunction "1_1") (pintype "passive"))
      (node (ref "C20") (pin "1") (pinfunction "1_1") (pintype "passive"))
      (node (ref "C22") (pin "1") (pinfunction "1_1") (pintype "passive"))
      (node (ref "C24") (pin "1") (pinfunction "1_1") (pintype "passive"))
      (node (ref "C26") (pin "1") (pinfunction "1_1") (pintype "passive"))
      (node (ref "C28") (pin "1") (pinfunction "1_1") (pintype "passive"))
      (node (ref "C3") (pin "1") (pinfunction "1_1") (pintype "passive"))
      (node (ref "C30") (pin "1") (pinfunction "1_1") (pintype "passive"))
      (node (ref "C32") (pin "1") (pinfunction "1_1") (pintype "passive"))
      (node (ref "C4") (pin "1") (pinfunction "1_1") (pintype "passive"))
      (node (ref "C6") (pin "1") (pinfunction "1_1") (pintype "passive"))
      (node (ref "C8") (pin "1") (pinfunction "1_1") (pintype "passive"))
      (node (ref "D19") (pin "A") (pinfunction "A_A") (pintype "passive"))
      (node (ref "D20") (pin "A") (pinfunction "A_A") (pintype "passive"))
      (node (ref "D21") (pin "A") (pinfunction "A_A") (pintype "passive"))
      (node (ref "D22") (pin "A") (pinfunction "A_A") (pintype "passive"))
      (node (ref "D23") (pin "A") (pinfunction "A_A") (pintype "passive"))
      (node (ref "D24") (pin "A") (pinfunction "A_A") (pintype "passive"))
      (node (ref "D25") (pin "A") (pinfunction "A_A") (pintype "passive"))
      (node (ref "D26") (pin "A") (pinfunction "A_A") (pintype "passive"))
      (node (ref "D27") (pin "A") (pinfunction "A_A") (pintype "passive"))
      (node (ref "D28") (pin "A") (pinfunction "A_A") (pintype "passive"))
      (node (ref "D29") (pin "A") (pinfunction "A_A") (pintype "passive"))
      (node (ref "D30") (pin "A") (pinfunction "A_A") (pintype "passive"))
      (node (ref "D31") (pin "A") (pinfunction "A_A") (pintype "passive"))
      (node (ref "D32") (pin "A") (pinfunction "A_A") (pintype "passive"))
      (node (ref "D33") (pin "A") (pinfunction "A_A") (pintype "passive"))
      (node (ref "D34") (pin "A") (pinfunction "A_A") (pintype "passive"))
      (node (ref "SV32") (pin "2") (pinfunction "2_2") (pintype "passive"))
      (node (ref "SV32") (pin "20") (pinfunction "20_20") (pintype "passive"))
      (node (ref "U1") (pin "2") (pinfunction "-IN_2") (pintype "input"))
      (node (ref "U1") (pin "4") (pinfunction "V-_4") (pintype "power_in"))
      (node (ref "U10") (pin "2") (pinfunction "-IN_2") (pintype "input"))
      (node (ref "U10") (pin "4") (pinfunction "V-_4") (pintype "power_in"))
      (node (ref "U11") (pin "2") (pinfunction "-IN_2") (pintype "input"))
      (node (ref "U11") (pin "4") (pinfunction "V-_4") (pintype "power_in"))
      (node (ref "U12") (pin "2") (pinfunction "-IN_2") (pintype "input"))
      (node (ref "U12") (pin "4") (pinfunction "V-_4") (pintype "power_in"))
      (node (ref "U13") (pin "2") (pinfunction "-IN_2") (pintype "input"))
      (node (ref "U13") (pin "4") (pinfunction "V-_4") (pintype "power_in"))
      (node (ref "U14") (pin "2") (pinfunction "-IN_2") (pintype "input"))
      (node (ref "U14") (pin "4") (pinfunction "V-_4") (pintype "power_in"))
      (node (ref "U15") (pin "2") (pinfunction "-IN_2") (pintype "input"))
      (node (ref "U15") (pin "4") (pinfunction "V-_4") (pintype "power_in"))
      (node (ref "U16") (pin "2") (pinfunction "-IN_2") (pintype "input"))
      (node (ref "U16") (pin "4") (pinfunction "V-_4") (pintype "power_in"))
      (node (ref "U2") (pin "2") (pinfunction "-IN_2") (pintype "input"))
      (node (ref "U2") (pin "4") (pinfunction "V-_4") (pintype "power_in"))
      (node (ref "U3") (pin "2") (pinfunction "-IN_2") (pintype "input"))
      (node (ref "U3") (pin "4") (pinfunction "V-_4") (pintype "power_in"))
      (node (ref "U4") (pin "2") (pinfunction "-IN_2") (pintype "input"))
      (node (ref "U4") (pin "4") (pinfunction "V-_4") (pintype "power_in"))
      (node (ref "U5") (pin "2") (pinfunction "-IN_2") (pintype "input"))
      (node (ref "U5") (pin "4") (pinfunction "V-_4") (pintype "power_in"))
      (node (ref "U6") (pin "2") (pinfunction "-IN_2") (pintype "input"))
      (node (ref "U6") (pin "4") (pinfunction "V-_4") (pintype "power_in"))
      (node (ref "U7") (pin "2") (pinfunction "-IN_2") (pintype "input"))
      (node (ref "U7") (pin "4") (pinfunction "V-_4") (pintype "power_in"))
      (node (ref "U8") (pin "2") (pinfunction "-IN_2") (pintype "input"))
      (node (ref "U8") (pin "4") (pinfunction "V-_4") (pintype "power_in"))
      (node (ref "U9") (pin "2") (pinfunction "-IN_2") (pintype "input"))
      (node (ref "U9") (pin "4") (pinfunction "V-_4") (pintype "power_in"))
    )
    (net (code "19") (name "/GND_DIG") (class "Default")
      (node (ref "D1") (pin "C") (pinfunction "C_C") (pintype "passive"))
      (node (ref "D10") (pin "C") (pinfunction "C_C") (pintype "passive"))
      (node (ref "D11") (pin "C") (pinfunction "C_C") (pintype "passive"))
      (node (ref "D12") (pin "C") (pinfunction "C_C") (pintype "passive"))
      (node (ref "D13") (pin "C") (pinfunction "C_C") (pintype "passive"))
      (node (ref "D14") (pin "C") (pinfunction "C_C") (pintype "passive"))
      (node (ref "D15") (pin "C") (pinfunction "C_C") (pintype "passive"))
      (node (ref "D16") (pin "C") (pinfunction "C_C") (pintype "passive"))
      (node (ref "D17") (pin "C") (pinfunction "C_C") (pintype "passive"))
      (node (ref "D18") (pin "C") (pinfunction "C_C") (pintype "passive"))
      (node (ref "D2") (pin "C") (pinfunction "C_C") (pintype "passive"))
      (node (ref "D3") (pin "C") (pinfunction "C_C") (pintype "passive"))
      (node (ref "D4") (pin "C") (pinfunction "C_C") (pintype "passive"))
      (node (ref "D5") (pin "C") (pinfunction "C_C") (pintype "passive"))
      (node (ref "D6") (pin "C") (pinfunction "C_C") (pintype "passive"))
      (node (ref "D7") (pin "C") (pinfunction "C_C") (pintype "passive"))
      (node (ref "D8") (pin "C") (pinfunction "C_C") (pintype "passive"))
      (node (ref "D9") (pin "C") (pinfunction "C_C") (pintype "passive"))
      (node (ref "SV31") (pin "11") (pinfunction "11_11") (pintype "passive"))
      (node (ref "SV31") (pin "9") (pinfunction "9_9") (pintype "passive"))
    )
    (net (code "20") (name "/VDD_ANA") (class "Default")
      (node (ref "SV32") (pin "1") (pinfunction "1_1") (pintype "passive"))
      (node (ref "SV32") (pin "19") (pinfunction "19_19") (pintype "passive"))
      (node (ref "U1") (pin "7") (pinfunction "V+_7") (pintype "power_in"))
      (node (ref "U10") (pin "7") (pinfunction "V+_7") (pintype "power_in"))
      (node (ref "U11") (pin "7") (pinfunction "V+_7") (pintype "power_in"))
      (node (ref "U12") (pin "7") (pinfunction "V+_7") (pintype "power_in"))
      (node (ref "U13") (pin "7") (pinfunction "V+_7") (pintype "power_in"))
      (node (ref "U14") (pin "7") (pinfunction "V+_7") (pintype "power_in"))
      (node (ref "U15") (pin "7") (pinfunction "V+_7") (pintype "power_in"))
      (node (ref "U16") (pin "7") (pinfunction "V+_7") (pintype "power_in"))
      (node (ref "U2") (pin "7") (pinfunction "V+_7") (pintype "power_in"))
      (node (ref "U3") (pin "7") (pinfunction "V+_7") (pintype "power_in"))
      (node (ref "U4") (pin "7") (pinfunction "V+_7") (pintype "power_in"))
      (node (ref "U5") (pin "7") (pinfunction "V+_7") (pintype "power_in"))
      (node (ref "U6") (pin "7") (pinfunction "V+_7") (pintype "power_in"))
      (node (ref "U7") (pin "7") (pinfunction "V+_7") (pintype "power_in"))
      (node (ref "U8") (pin "7") (pinfunction "V+_7") (pintype "power_in"))
      (node (ref "U9") (pin "7") (pinfunction "V+_7") (pintype "power_in"))
    )
    (net (code "21") (name "/VLED1") (class "Default")
      (node (ref "D1") (pin "A") (pinfunction "A_A") (pintype "passive"))
      (node (ref "SV31") (pin "12") (pinfunction "12_12") (pintype "passive"))
    )
    (net (code "22") (name "/VLED2") (class "Default")
      (node (ref "D2") (pin "A") (pinfunction "A_A") (pintype "passive"))
      (node (ref "SV31") (pin "10") (pinfunction "10_10") (pintype "passive"))
    )
    (net (code "23") (name "/VLED3") (class "Default")
      (node (ref "D3") (pin "A") (pinfunction "A_A") (pintype "passive"))
      (node (ref "SV31") (pin "13") (pinfunction "13_13") (pintype "passive"))
    )
    (net (code "24") (name "/VLED4") (class "Default")
      (node (ref "D4") (pin "A") (pinfunction "A_A") (pintype "passive"))
      (node (ref "SV31") (pin "7") (pinfunction "7_7") (pintype "passive"))
    )
    (net (code "25") (name "/VLED5") (class "Default")
      (node (ref "D5") (pin "A") (pinfunction "A_A") (pintype "passive"))
      (node (ref "SV31") (pin "14") (pinfunction "14_14") (pintype "passive"))
    )
    (net (code "26") (name "/VLED6") (class "Default")
      (node (ref "D6") (pin "A") (pinfunction "A_A") (pintype "passive"))
      (node (ref "SV31") (pin "8") (pinfunction "8_8") (pintype "passive"))
    )
    (net (code "27") (name "/VLED7") (class "Default")
      (node (ref "D7") (pin "A") (pinfunction "A_A") (pintype "passive"))
      (node (ref "SV31") (pin "15") (pinfunction "15_15") (pintype "passive"))
    )
    (net (code "28") (name "/VLED8") (class "Default")
      (node (ref "D8") (pin "A") (pinfunction "A_A") (pintype "passive"))
      (node (ref "SV31") (pin "5") (pinfunction "5_5") (pintype "passive"))
    )
    (net (code "29") (name "/VLED9") (class "Default")
      (node (ref "D9") (pin "A") (pinfunction "A_A") (pintype "passive"))
      (node (ref "SV31") (pin "16") (pinfunction "16_16") (pintype "passive"))
    )
    (net (code "30") (name "/VLED10") (class "Default")
      (node (ref "D10") (pin "A") (pinfunction "A_A") (pintype "passive"))
      (node (ref "SV31") (pin "6") (pinfunction "6_6") (pintype "passive"))
    )
    (net (code "31") (name "/VLED11") (class "Default")
      (node (ref "D11") (pin "A") (pinfunction "A_A") (pintype "passive"))
      (node (ref "SV31") (pin "17") (pinfunction "17_17") (pintype "passive"))
    )
    (net (code "32") (name "/VLED12") (class "Default")
      (node (ref "D12") (pin "A") (pinfunction "A_A") (pintype "passive"))
      (node (ref "SV31") (pin "3") (pinfunction "3_3") (pintype "passive"))
    )
    (net (code "33") (name "/VLED13") (class "Default")
      (node (ref "D13") (pin "A") (pinfunction "A_A") (pintype "passive"))
      (node (ref "SV31") (pin "18") (pinfunction "18_18") (pintype "passive"))
    )
    (net (code "34") (name "/VLED14") (class "Default")
      (node (ref "D14") (pin "A") (pinfunction "A_A") (pintype "passive"))
      (node (ref "SV31") (pin "4") (pinfunction "4_4") (pintype "passive"))
    )
    (net (code "35") (name "/VLED15") (class "Default")
      (node (ref "D15") (pin "A") (pinfunction "A_A") (pintype "passive"))
      (node (ref "SV31") (pin "19") (pinfunction "19_19") (pintype "passive"))
    )
    (net (code "36") (name "/VLED16") (class "Default")
      (node (ref "D16") (pin "A") (pinfunction "A_A") (pintype "passive"))
      (node (ref "SV31") (pin "1") (pinfunction "1_1") (pintype "passive"))
    )
    (net (code "37") (name "/VLED17") (class "Default")
      (node (ref "D17") (pin "A") (pinfunction "A_A") (pintype "passive"))
      (node (ref "SV31") (pin "20") (pinfunction "20_20") (pintype "passive"))
    )
    (net (code "38") (name "/VLED18") (class "Default")
      (node (ref "D18") (pin "A") (pinfunction "A_A") (pintype "passive"))
      (node (ref "SV31") (pin "2") (pinfunction "2_2") (pintype "passive"))
    )
  )
)
